# Level_shifter.net
KiCad netlist of a schematic drawn in Altium Designer
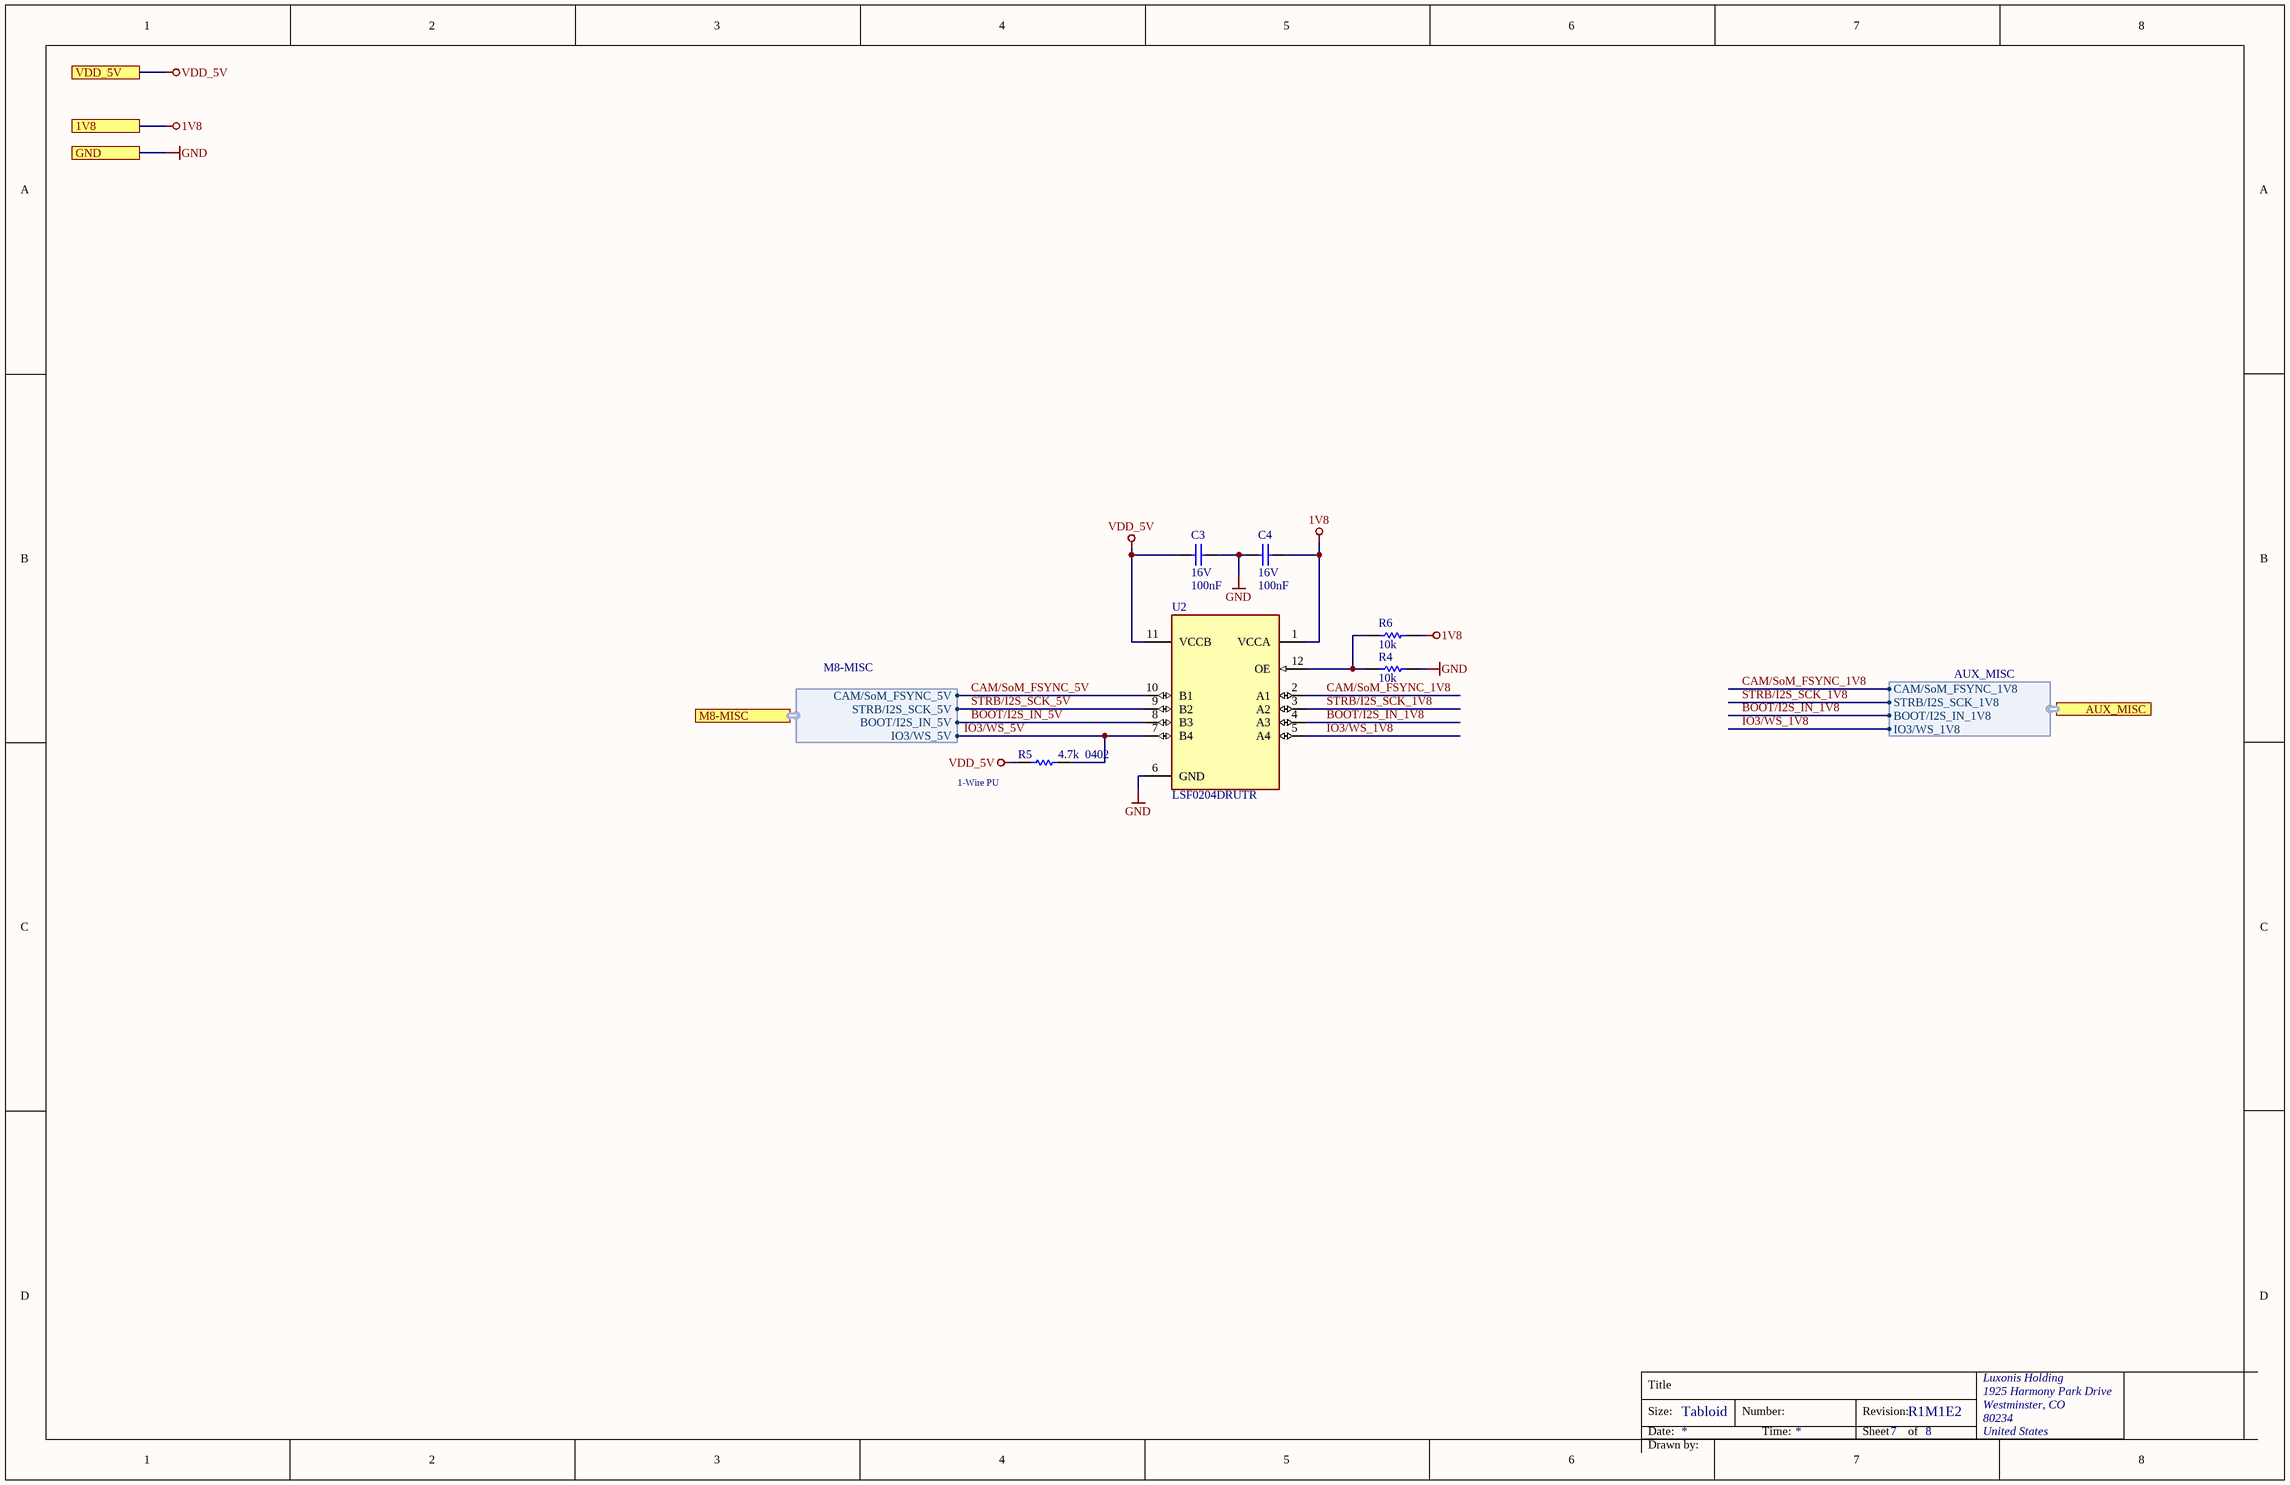
[diagram p0: Level_shifter.SchDoc]

(export (version "E")
  (design (tool "Eeschema 10.0.6"))
  (components
    (comp (ref "C3")
      (value "100nF")
      (footprint "CAPC0402(1005)60_N")
      (description "CAP CER 0.1UF 16V X7R 0402 10%")
      (fields
        (field (name "VOLTAGE RATING") "16V")
        (field (name "TOLERANCE") "10%")
        (field (name "Comment") "CL05B104KO5NFNC")
      )
      (libsource (lib "Luxonis LLC") (part "GRM188R61C475KAAJD"))
    )
    (comp (ref "C4")
      (value "100nF")
      (footprint "CAPC0402(1005)60_N")
      (description "CAP CER 0.1UF 16V X7R 0402 10%")
      (fields
        (field (name "VOLTAGE RATING") "16V")
        (field (name "TOLERANCE") "10%")
        (field (name "Comment") "CL05B104KO5NFNC")
      )
      (libsource (lib "Luxonis LLC") (part "GRM188R61C475KAAJD"))
    )
    (comp (ref "R4")
      (value "10k")
      (footprint "RESC0402(1005)_N")
      (description "RES SMD 10K OHM 1% 1/16W 0402")
      (fields (field (name "TOLERANCE") "1%") (field (name "Comment") "RC0402FR-1310KL"))
      (libsource (lib "Luxonis LLC") (part "RC0402FR-0722RL_1"))
    )
    (comp (ref "R5")
      (value "4.7k")
      (footprint "RESC0402(1005)_N")
      (description "RES SMD 4.7K OHM 1% 1/16W 0402")
      (fields
        (field (name "CASE/PACKAGE") "0402")
        (field (name "TOLERANCE") "1%")
        (field (name "Comment") "RC0402FR-074K7L")
      )
      (libsource (lib "Luxonis LLC") (part "Default resistor symbol"))
    )
    (comp (ref "R6")
      (value "10k")
      (footprint "RESC0402(1005)_N")
      (description "RES SMD 10K OHM 1% 1/16W 0402")
      (fields (field (name "TOLERANCE") "1%") (field (name "Comment") "RC0402FR-1310KL"))
      (libsource (lib "Luxonis LLC") (part "RC0402FR-0722RL_1"))
    )
    (comp (ref "U2")
      (value "LSF0204DRUTR")
      (footprint "LSF0204DRUTR")
      (description "Voltage Level Translator Bidirectional 1 Circuit 4 Channel 100Mbps 12-UQFN _1.7x2_")
      (fields (field (name "MF") "Texas Instruments"))
      (libsource (lib "Luxonis LLC") (part "LSF0204DRUTR"))
    )
  )
  (nets
    (net (code "3") (name "/BOOT{slash}I2S_IN_1V8") (class "Default")
      (node (ref "U2") (pin "4") (pinfunction "A3_4") (pintype "bidirectional"))
    )
    (net (code "4") (name "/BOOT{slash}I2S_IN_5V") (class "Default")
      (node (ref "U2") (pin "8") (pinfunction "B3_8") (pintype "bidirectional"))
    )
    (net (code "5") (name "/CAM{slash}SoM_FSYNC_1V8") (class "Default")
      (node (ref "U2") (pin "2") (pinfunction "A1_2") (pintype "bidirectional"))
    )
    (net (code "6") (name "/CAM{slash}SoM_FSYNC_5V") (class "Default")
      (node (ref "U2") (pin "10") (pinfunction "B1_10") (pintype "bidirectional"))
    )
    (net (code "7") (name "/IO3{slash}WS_1V8") (class "Default")
      (node (ref "U2") (pin "5") (pinfunction "A4_5") (pintype "bidirectional"))
    )
    (net (code "8") (name "/IO3{slash}WS_5V") (class "Default")
      (node (ref "R5") (pin "2") (pinfunction "2_2") (pintype "passive"))
      (node (ref "U2") (pin "7") (pinfunction "B4_7") (pintype "bidirectional"))
    )
    (net (code "9") (name "/STRB{slash}I2S_SCK_1V8") (class "Default")
      (node (ref "U2") (pin "3") (pinfunction "A2_3") (pintype "bidirectional"))
    )
    (net (code "10") (name "/STRB{slash}I2S_SCK_5V") (class "Default")
      (node (ref "U2") (pin "9") (pinfunction "B2_9") (pintype "bidirectional"))
    )
    (net (code "13") (name "1V8") (class "Default")
      (node (ref "C4") (pin "2") (pinfunction "2_2") (pintype "passive"))
      (node (ref "R6") (pin "2") (pinfunction "2_2") (pintype "passive"))
      (node (ref "U2") (pin "1") (pinfunction "VCCA_1") (pintype "power_in"))
    )
    (net (code "14") (name "GND") (class "Default")
      (node (ref "C3") (pin "2") (pinfunction "2_2") (pintype "passive"))
      (node (ref "C4") (pin "1") (pinfunction "1_1") (pintype "passive"))
      (node (ref "R4") (pin "2") (pinfunction "2_2") (pintype "passive"))
      (node (ref "U2") (pin "6") (pinfunction "GND_6") (pintype "power_in"))
    )
    (net (code "15") (name "Net-(U2-OE)") (class "Default")
      (node (ref "R4") (pin "1") (pinfunction "1_1") (pintype "passive"))
      (node (ref "R6") (pin "1") (pinfunction "1_1") (pintype "passive"))
      (node (ref "U2") (pin "12") (pinfunction "OE_12") (pintype "input"))
    )
    (net (code "16") (name "VDD_5V") (class "Default")
      (node (ref "C3") (pin "1") (pinfunction "1_1") (pintype "passive"))
      (node (ref "R5") (pin "1") (pinfunction "1_1") (pintype "passive"))
      (node (ref "U2") (pin "11") (pinfunction "VCCB_11") (pintype "power_in"))
    )
  )
)
